# Loconet_in-out_v3.net
KiCad netlist of a schematic drawn in EAGLE
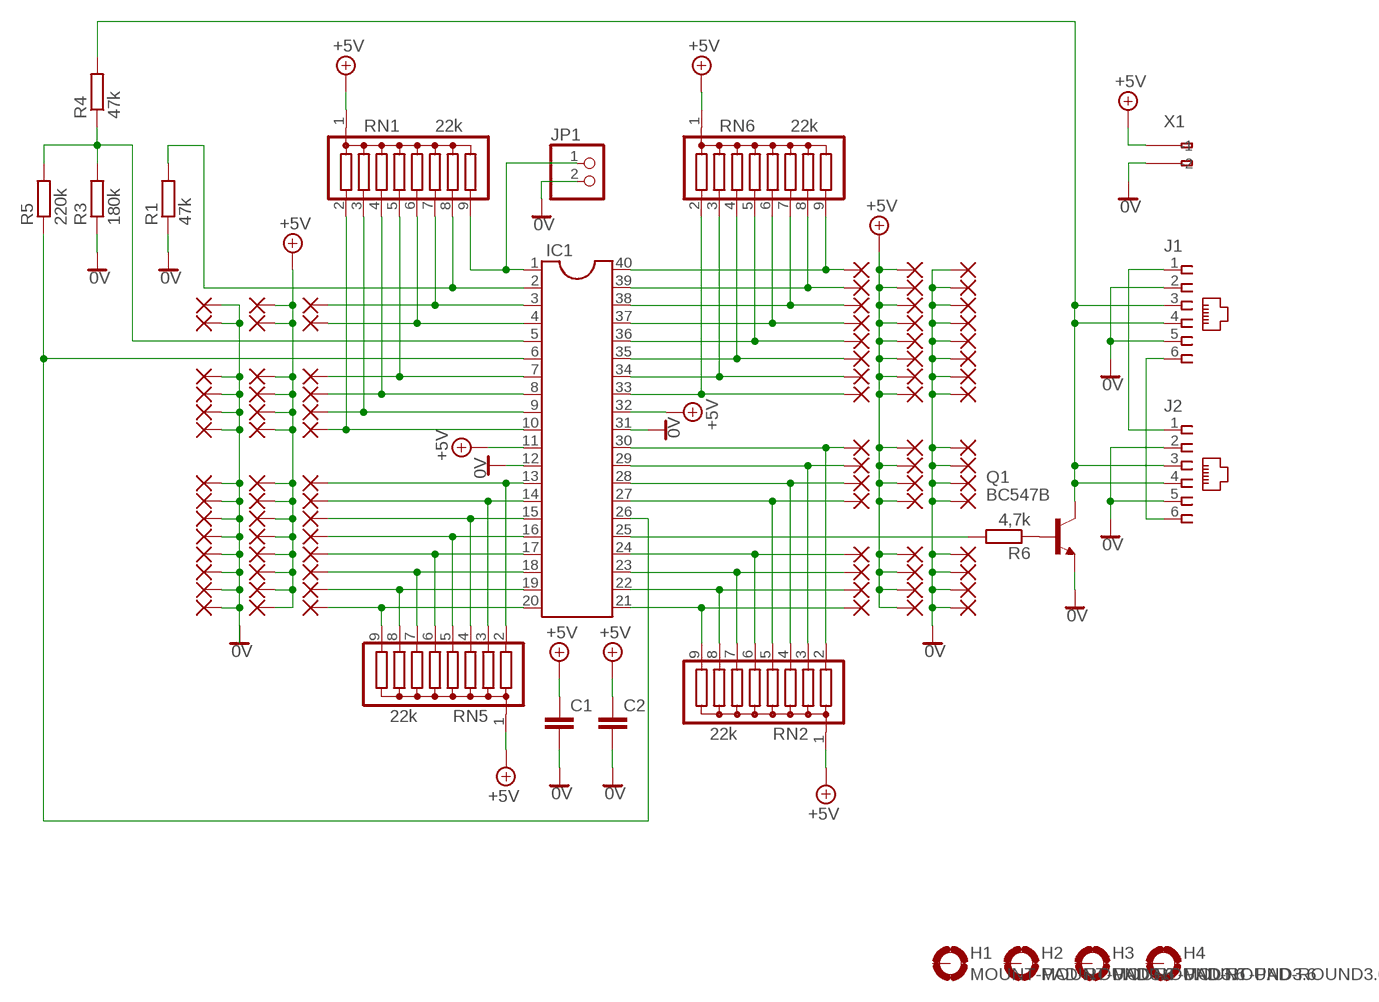
[diagram p0: schematic, sheet 1]

(export (version "E")
  (design (tool "Eeschema 10.0.6"))
  (components
    (comp (ref "0")
      (value "2,15/1,0")
      (footprint "eagle-import:2,15_1,0")
      (libsource (lib "eagle-import") (part "2,15/1,0"))
    )
    (comp (ref "1")
      (value "1")
      (footprint "eagle-import:2,15_1,0")
      (libsource (lib "eagle-import") (part "2,15/1,0"))
    )
    (comp (ref "2")
      (value "2,15/1,0")
      (footprint "eagle-import:2,15_1,0")
      (libsource (lib "eagle-import") (part "2,15/1,0"))
    )
    (comp (ref "3")
      (value "2,15/1,0")
      (footprint "eagle-import:2,15_1,0")
      (libsource (lib "eagle-import") (part "2,15/1,0"))
    )
    (comp (ref "4")
      (value "2,15/1,0")
      (footprint "eagle-import:2,15_1,0")
      (libsource (lib "eagle-import") (part "2,15/1,0"))
    )
    (comp (ref "5")
      (value "2,15/1,0")
      (footprint "eagle-import:2,15_1,0")
      (libsource (lib "eagle-import") (part "2,15/1,0"))
    )
    (comp (ref "6")
      (value "2,15/1,0")
      (footprint "eagle-import:2,15_1,0")
      (libsource (lib "eagle-import") (part "2,15/1,0"))
    )
    (comp (ref "7")
      (value "2,15/1,0")
      (footprint "eagle-import:2,15_1,0")
      (libsource (lib "eagle-import") (part "2,15/1,0"))
    )
    (comp (ref "8")
      (value "2,15/1,0")
      (footprint "eagle-import:2,15_1,0")
      (libsource (lib "eagle-import") (part "2,15/1,0"))
    )
    (comp (ref "9")
      (value "2,15/1,0")
      (footprint "eagle-import:2,15_1,0")
      (libsource (lib "eagle-import") (part "2,15/1,0"))
    )
    (comp (ref "10")
      (value "2,15/1,0")
      (footprint "eagle-import:2,15_1,0")
      (libsource (lib "eagle-import") (part "2,15/1,0"))
    )
    (comp (ref "11")
      (value "2,15/1,0")
      (footprint "eagle-import:2,15_1,0")
      (libsource (lib "eagle-import") (part "2,15/1,0"))
    )
    (comp (ref "12")
      (value "2,15/1,0")
      (footprint "eagle-import:2,15_1,0")
      (libsource (lib "eagle-import") (part "2,15/1,0"))
    )
    (comp (ref "13")
      (value "2,15/1,0")
      (footprint "eagle-import:2,15_1,0")
      (libsource (lib "eagle-import") (part "2,15/1,0"))
    )
    (comp (ref "14")
      (value "2,15/1,0")
      (footprint "eagle-import:2,15_1,0")
      (libsource (lib "eagle-import") (part "2,15/1,0"))
    )
    (comp (ref "15")
      (value "2,15/1,0")
      (footprint "eagle-import:2,15_1,0")
      (libsource (lib "eagle-import") (part "2,15/1,0"))
    )
    (comp (ref "16")
      (value "2,15/1,0")
      (footprint "eagle-import:2,15_1,0")
      (libsource (lib "eagle-import") (part "2,15/1,0"))
    )
    (comp (ref "17")
      (value "2,15/1,0")
      (footprint "eagle-import:2,15_1,0")
      (libsource (lib "eagle-import") (part "2,15/1,0"))
    )
    (comp (ref "18")
      (value "2,15/1,0")
      (footprint "eagle-import:2,15_1,0")
      (libsource (lib "eagle-import") (part "2,15/1,0"))
    )
    (comp (ref "19")
      (value "2,15/1,0")
      (footprint "eagle-import:2,15_1,0")
      (libsource (lib "eagle-import") (part "2,15/1,0"))
    )
    (comp (ref "20")
      (value "2,15/1,0")
      (footprint "eagle-import:2,15_1,0")
      (libsource (lib "eagle-import") (part "2,15/1,0"))
    )
    (comp (ref "21")
      (value "2,15/1,0")
      (footprint "eagle-import:2,15_1,0")
      (libsource (lib "eagle-import") (part "2,15/1,0"))
    )
    (comp (ref "22")
      (value "2,15/1,0")
      (footprint "eagle-import:2,15_1,0")
      (libsource (lib "eagle-import") (part "2,15/1,0"))
    )
    (comp (ref "23")
      (value "2,15/1,0")
      (footprint "eagle-import:2,15_1,0")
      (libsource (lib "eagle-import") (part "2,15/1,0"))
    )
    (comp (ref "24")
      (value "2,15/1,0")
      (footprint "eagle-import:2,15_1,0")
      (libsource (lib "eagle-import") (part "2,15/1,0"))
    )
    (comp (ref "25")
      (value "2,15/1,0")
      (footprint "eagle-import:2,15_1,0")
      (libsource (lib "eagle-import") (part "2,15/1,0"))
    )
    (comp (ref "26")
      (value "2,15/1,0")
      (footprint "eagle-import:2,15_1,0")
      (libsource (lib "eagle-import") (part "2,15/1,0"))
    )
    (comp (ref "27")
      (value "2,15/1,0")
      (footprint "eagle-import:2,15_1,0")
      (libsource (lib "eagle-import") (part "2,15/1,0"))
    )
    (comp (ref "28")
      (value "2,15/1,0")
      (footprint "eagle-import:2,15_1,0")
      (libsource (lib "eagle-import") (part "2,15/1,0"))
    )
    (comp (ref "29")
      (value "2,15/1,0")
      (footprint "eagle-import:2,15_1,0")
      (libsource (lib "eagle-import") (part "2,15/1,0"))
    )
    (comp (ref "30")
      (value "2,15/1,0")
      (footprint "eagle-import:2,15_1,0")
      (libsource (lib "eagle-import") (part "2,15/1,0"))
    )
    (comp (ref "C1")
      (value "C-EU025-024X044")
      (footprint "eagle-import:C025-024X044")
      (libsource (lib "eagle-import") (part "C-EU025-024X044"))
    )
    (comp (ref "C2")
      (value "C-EU025-024X044")
      (footprint "eagle-import:C025-024X044")
      (libsource (lib "eagle-import") (part "C-EU025-024X044"))
    )
    (comp (ref "H1")
      (value "MOUNT-PAD-ROUND3.6")
      (footprint "eagle-import:3,6-PAD")
      (libsource (lib "eagle-import") (part "MOUNT-PAD-ROUND3.6"))
    )
    (comp (ref "H2")
      (value "MOUNT-PAD-ROUND3.6")
      (footprint "eagle-import:3,6-PAD")
      (libsource (lib "eagle-import") (part "MOUNT-PAD-ROUND3.6"))
    )
    (comp (ref "H3")
      (value "MOUNT-PAD-ROUND3.6")
      (footprint "eagle-import:3,6-PAD")
      (libsource (lib "eagle-import") (part "MOUNT-PAD-ROUND3.6"))
    )
    (comp (ref "H4")
      (value "MOUNT-PAD-ROUND3.6")
      (footprint "eagle-import:3,6-PAD")
      (libsource (lib "eagle-import") (part "MOUNT-PAD-ROUND3.6"))
    )
    (comp (ref "IC1")
      (value "DIL40")
      (footprint "eagle-import:DIL40")
      (libsource (lib "eagle-import") (part "DIL40"))
    )
    (comp (ref "J1")
      (value "520250-3")
      (footprint "eagle-import:520250-3")
      (libsource (lib "eagle-import") (part "520250-3"))
    )
    (comp (ref "J2")
      (value "520250-3")
      (footprint "eagle-import:520250-3")
      (libsource (lib "eagle-import") (part "520250-3"))
    )
    (comp (ref "JP1")
      (value "PINHD-1X2")
      (footprint "eagle-import:1X02")
      (libsource (lib "eagle-import") (part "PINHD-1X2"))
    )
    (comp (ref "PAD1")
      (value "2,15/1,0")
      (footprint "eagle-import:2,15_1,0")
      (libsource (lib "eagle-import") (part "2,15/1,0"))
    )
    (comp (ref "PAD2")
      (value "2,15/1,0")
      (footprint "eagle-import:2,15_1,0")
      (libsource (lib "eagle-import") (part "2,15/1,0"))
    )
    (comp (ref "PAD3")
      (value "2,15/1,0")
      (footprint "eagle-import:2,15_1,0")
      (libsource (lib "eagle-import") (part "2,15/1,0"))
    )
    (comp (ref "PAD4")
      (value "2,15/1,0")
      (footprint "eagle-import:2,15_1,0")
      (libsource (lib "eagle-import") (part "2,15/1,0"))
    )
    (comp (ref "PAD5")
      (value "2,15/1,0")
      (footprint "eagle-import:2,15_1,0")
      (libsource (lib "eagle-import") (part "2,15/1,0"))
    )
    (comp (ref "PAD6")
      (value "2,15/1,0")
      (footprint "eagle-import:2,15_1,0")
      (libsource (lib "eagle-import") (part "2,15/1,0"))
    )
    (comp (ref "PAD7")
      (value "2,15/1,0")
      (footprint "eagle-import:2,15_1,0")
      (libsource (lib "eagle-import") (part "2,15/1,0"))
    )
    (comp (ref "PAD8")
      (value "2,15/1,0")
      (footprint "eagle-import:2,15_1,0")
      (libsource (lib "eagle-import") (part "2,15/1,0"))
    )
    (comp (ref "PAD9")
      (value "2,15/1,0")
      (footprint "eagle-import:2,15_1,0")
      (libsource (lib "eagle-import") (part "2,15/1,0"))
    )
    (comp (ref "PAD10")
      (value "2,15/1,0")
      (footprint "eagle-import:2,15_1,0")
      (libsource (lib "eagle-import") (part "2,15/1,0"))
    )
    (comp (ref "PAD11")
      (value "2,15/1,0")
      (footprint "eagle-import:2,15_1,0")
      (libsource (lib "eagle-import") (part "2,15/1,0"))
    )
    (comp (ref "PAD12")
      (value "2,15/1,0")
      (footprint "eagle-import:2,15_1,0")
      (libsource (lib "eagle-import") (part "2,15/1,0"))
    )
    (comp (ref "PAD13")
      (value "2,15/1,0")
      (footprint "eagle-import:2,15_1,0")
      (libsource (lib "eagle-import") (part "2,15/1,0"))
    )
    (comp (ref "PAD14")
      (value "2,15/1,0")
      (footprint "eagle-import:2,15_1,0")
      (libsource (lib "eagle-import") (part "2,15/1,0"))
    )
    (comp (ref "PAD15")
      (value "2,15/1,0")
      (footprint "eagle-import:2,15_1,0")
      (libsource (lib "eagle-import") (part "2,15/1,0"))
    )
    (comp (ref "PAD16")
      (value "2,15/1,0")
      (footprint "eagle-import:2,15_1,0")
      (libsource (lib "eagle-import") (part "2,15/1,0"))
    )
    (comp (ref "PAD17")
      (value "2,15/1,0")
      (footprint "eagle-import:2,15_1,0")
      (libsource (lib "eagle-import") (part "2,15/1,0"))
    )
    (comp (ref "PAD18")
      (value "2,15/1,0")
      (footprint "eagle-import:2,15_1,0")
      (libsource (lib "eagle-import") (part "2,15/1,0"))
    )
    (comp (ref "PAD19")
      (value "2,15/1,0")
      (footprint "eagle-import:2,15_1,0")
      (libsource (lib "eagle-import") (part "2,15/1,0"))
    )
    (comp (ref "PAD20")
      (value "2,15/1,0")
      (footprint "eagle-import:2,15_1,0")
      (libsource (lib "eagle-import") (part "2,15/1,0"))
    )
    (comp (ref "PAD21")
      (value "2,15/1,0")
      (footprint "eagle-import:2,15_1,0")
      (libsource (lib "eagle-import") (part "2,15/1,0"))
    )
    (comp (ref "PAD22")
      (value "2,15/1,0")
      (footprint "eagle-import:2,15_1,0")
      (libsource (lib "eagle-import") (part "2,15/1,0"))
    )
    (comp (ref "PAD23")
      (value "2,15/1,0")
      (footprint "eagle-import:2,15_1,0")
      (libsource (lib "eagle-import") (part "2,15/1,0"))
    )
    (comp (ref "PAD24")
      (value "2,15/1,0")
      (footprint "eagle-import:2,15_1,0")
      (libsource (lib "eagle-import") (part "2,15/1,0"))
    )
    (comp (ref "PAD25")
      (value "2,15/1,0")
      (footprint "eagle-import:2,15_1,0")
      (libsource (lib "eagle-import") (part "2,15/1,0"))
    )
    (comp (ref "PAD26")
      (value "2,15/1,0")
      (footprint "eagle-import:2,15_1,0")
      (libsource (lib "eagle-import") (part "2,15/1,0"))
    )
    (comp (ref "PAD27")
      (value "2,15/1,0")
      (footprint "eagle-import:2,15_1,0")
      (libsource (lib "eagle-import") (part "2,15/1,0"))
    )
    (comp (ref "PAD28")
      (value "2,15/1,0")
      (footprint "eagle-import:2,15_1,0")
      (libsource (lib "eagle-import") (part "2,15/1,0"))
    )
    (comp (ref "PAD29")
      (value "2,15/1,0")
      (footprint "eagle-import:2,15_1,0")
      (libsource (lib "eagle-import") (part "2,15/1,0"))
    )
    (comp (ref "PAD30")
      (value "2,15/1,0")
      (footprint "eagle-import:2,15_1,0")
      (libsource (lib "eagle-import") (part "2,15/1,0"))
    )
    (comp (ref "PAD33")
      (value "2,15/1,0")
      (footprint "eagle-import:2,15_1,0")
      (libsource (lib "eagle-import") (part "2,15/1,0"))
    )
    (comp (ref "PAD35")
      (value "2,15/1,0")
      (footprint "eagle-import:2,15_1,0")
      (libsource (lib "eagle-import") (part "2,15/1,0"))
    )
    (comp (ref "PAD37")
      (value "2,15/1,0")
      (footprint "eagle-import:2,15_1,0")
      (libsource (lib "eagle-import") (part "2,15/1,0"))
    )
    (comp (ref "PAD39")
      (value "2,15/1,0")
      (footprint "eagle-import:2,15_1,0")
      (libsource (lib "eagle-import") (part "2,15/1,0"))
    )
    (comp (ref "PAD41")
      (value "2,15/1,0")
      (footprint "eagle-import:2,15_1,0")
      (libsource (lib "eagle-import") (part "2,15/1,0"))
    )
    (comp (ref "PAD43")
      (value "2,15/1,0")
      (footprint "eagle-import:2,15_1,0")
      (libsource (lib "eagle-import") (part "2,15/1,0"))
    )
    (comp (ref "PAD52")
      (value "2,15/1,0")
      (footprint "eagle-import:2,15_1,0")
      (libsource (lib "eagle-import") (part "2,15/1,0"))
    )
    (comp (ref "PAD53")
      (value "2,15/1,0")
      (footprint "eagle-import:2,15_1,0")
      (libsource (lib "eagle-import") (part "2,15/1,0"))
    )
    (comp (ref "PAD54")
      (value "2,15/1,0")
      (footprint "eagle-import:2,15_1,0")
      (libsource (lib "eagle-import") (part "2,15/1,0"))
    )
    (comp (ref "PAD55")
      (value "2,15/1,0")
      (footprint "eagle-import:2,15_1,0")
      (libsource (lib "eagle-import") (part "2,15/1,0"))
    )
    (comp (ref "PAD56")
      (value "2,15/1,0")
      (footprint "eagle-import:2,15_1,0")
      (libsource (lib "eagle-import") (part "2,15/1,0"))
    )
    (comp (ref "PAD57")
      (value "2,15/1,0")
      (footprint "eagle-import:2,15_1,0")
      (libsource (lib "eagle-import") (part "2,15/1,0"))
    )
    (comp (ref "PAD58")
      (value "2,15/1,0")
      (footprint "eagle-import:2,15_1,0")
      (libsource (lib "eagle-import") (part "2,15/1,0"))
    )
    (comp (ref "PAD59")
      (value "2,15/1,0")
      (footprint "eagle-import:2,15_1,0")
      (libsource (lib "eagle-import") (part "2,15/1,0"))
    )
    (comp (ref "PAD60")
      (value "2,15/1,0")
      (footprint "eagle-import:2,15_1,0")
      (libsource (lib "eagle-import") (part "2,15/1,0"))
    )
    (comp (ref "PAD61")
      (value "2,15/1,0")
      (footprint "eagle-import:2,15_1,0")
      (libsource (lib "eagle-import") (part "2,15/1,0"))
    )
    (comp (ref "PAD62")
      (value "2,15/1,0")
      (footprint "eagle-import:2,15_1,0")
      (libsource (lib "eagle-import") (part "2,15/1,0"))
    )
    (comp (ref "PAD63")
      (value "2,15/1,0")
      (footprint "eagle-import:2,15_1,0")
      (libsource (lib "eagle-import") (part "2,15/1,0"))
    )
    (comp (ref "PAD64")
      (value "2,15/1,0")
      (footprint "eagle-import:2,15_1,0")
      (libsource (lib "eagle-import") (part "2,15/1,0"))
    )
    (comp (ref "PAD65")
      (value "2,15/1,0")
      (footprint "eagle-import:2,15_1,0")
      (libsource (lib "eagle-import") (part "2,15/1,0"))
    )
    (comp (ref "PAD66")
      (value "2,15/1,0")
      (footprint "eagle-import:2,15_1,0")
      (libsource (lib "eagle-import") (part "2,15/1,0"))
    )
    (comp (ref "PAD67")
      (value "2,15/1,0")
      (footprint "eagle-import:2,15_1,0")
      (libsource (lib "eagle-import") (part "2,15/1,0"))
    )
    (comp (ref "PAD68")
      (value "2,15/1,0")
      (footprint "eagle-import:2,15_1,0")
      (libsource (lib "eagle-import") (part "2,15/1,0"))
    )
    (comp (ref "PAD69")
      (value "2,15/1,0")
      (footprint "eagle-import:2,15_1,0")
      (libsource (lib "eagle-import") (part "2,15/1,0"))
    )
    (comp (ref "PAD70")
      (value "2,15/1,0")
      (footprint "eagle-import:2,15_1,0")
      (libsource (lib "eagle-import") (part "2,15/1,0"))
    )
    (comp (ref "PAD71")
      (value "2,15/1,0")
      (footprint "eagle-import:2,15_1,0")
      (libsource (lib "eagle-import") (part "2,15/1,0"))
    )
    (comp (ref "PAD72")
      (value "2,15/1,0")
      (footprint "eagle-import:2,15_1,0")
      (libsource (lib "eagle-import") (part "2,15/1,0"))
    )
    (comp (ref "PAD73")
      (value "2,15/1,0")
      (footprint "eagle-import:2,15_1,0")
      (libsource (lib "eagle-import") (part "2,15/1,0"))
    )
    (comp (ref "PAD74")
      (value "2,15/1,0")
      (footprint "eagle-import:2,15_1,0")
      (libsource (lib "eagle-import") (part "2,15/1,0"))
    )
    (comp (ref "Q1")
      (value "BC547B")
      (footprint "eagle-import:TO92")
      (libsource (lib "eagle-import") (part "BC547B"))
    )
    (comp (ref "R1")
      (value "47k")
      (footprint "eagle-import:0204_7")
      (libsource (lib "eagle-import") (part "R-EU_0204/7"))
    )
    (comp (ref "R3")
      (value "180k")
      (footprint "eagle-import:0204_7")
      (libsource (lib "eagle-import") (part "R-EU_0204/7"))
    )
    (comp (ref "R4")
      (value "47k")
      (footprint "eagle-import:0204_7")
      (libsource (lib "eagle-import") (part "R-EU_0204/7"))
    )
    (comp (ref "R5")
      (value "220k")
      (footprint "eagle-import:0204_7")
      (libsource (lib "eagle-import") (part "R-EU_0204/7"))
    )
    (comp (ref "R6")
      (value "4,7k")
      (footprint "eagle-import:0204_7")
      (libsource (lib "eagle-import") (part "R-EU_0204/7"))
    )
    (comp (ref "RN1")
      (value "22k")
      (footprint "eagle-import:SIL9")
      (libsource (lib "eagle-import") (part "G08R"))
    )
    (comp (ref "RN2")
      (value "22k")
      (footprint "eagle-import:SIL9")
      (libsource (lib "eagle-import") (part "G08R"))
    )
    (comp (ref "RN5")
      (value "22k")
      (footprint "eagle-import:SIL9")
      (libsource (lib "eagle-import") (part "G08R"))
    )
    (comp (ref "RN6")
      (value "22k")
      (footprint "eagle-import:SIL9")
      (libsource (lib "eagle-import") (part "G08R"))
    )
    (comp (ref "X1")
      (value "233-102")
      (footprint "eagle-import:233-102")
      (libsource (lib "eagle-import") (part "233-102"))
    )
  )
  (nets
    (net (code "1") (name "+5V") (class "Default")
      (node (ref "0") (pin "1") (pinfunction "P_1") (pintype "passive"))
      (node (ref "C1") (pin "1") (pinfunction "1_1") (pintype "passive"))
      (node (ref "C2") (pin "1") (pinfunction "1_1") (pintype "passive"))
      (node (ref "IC1") (pin "11") (pinfunction "11_11") (pintype "passive"))
      (node (ref "IC1") (pin "32") (pinfunction "32_32") (pintype "passive"))
      (node (ref "PAD33") (pin "1") (pinfunction "P_1") (pintype "passive"))
      (node (ref "PAD35") (pin "1") (pinfunction "P_1") (pintype "passive"))
      (node (ref "PAD37") (pin "1") (pinfunction "P_1") (pintype "passive"))
      (node (ref "PAD39") (pin "1") (pinfunction "P_1") (pintype "passive"))
      (node (ref "PAD41") (pin "1") (pinfunction "P_1") (pintype "passive"))
      (node (ref "PAD43") (pin "1") (pinfunction "P_1") (pintype "passive"))
      (node (ref "PAD52") (pin "1") (pinfunction "P_1") (pintype "passive"))
      (node (ref "PAD53") (pin "1") (pinfunction "P_1") (pintype "passive"))
      (node (ref "PAD54") (pin "1") (pinfunction "P_1") (pintype "passive"))
      (node (ref "PAD55") (pin "1") (pinfunction "P_1") (pintype "passive"))
      (node (ref "PAD56") (pin "1") (pinfunction "P_1") (pintype "passive"))
      (node (ref "PAD57") (pin "1") (pinfunction "P_1") (pintype "passive"))
      (node (ref "PAD58") (pin "1") (pinfunction "P_1") (pintype "passive"))
      (node (ref "PAD59") (pin "1") (pinfunction "P_1") (pintype "passive"))
      (node (ref "PAD60") (pin "1") (pinfunction "P_1") (pintype "passive"))
      (node (ref "PAD61") (pin "1") (pinfunction "P_1") (pintype "passive"))
      (node (ref "PAD62") (pin "1") (pinfunction "P_1") (pintype "passive"))
      (node (ref "PAD63") (pin "1") (pinfunction "P_1") (pintype "passive"))
      (node (ref "PAD64") (pin "1") (pinfunction "P_1") (pintype "passive"))
      (node (ref "PAD65") (pin "1") (pinfunction "P_1") (pintype "passive"))
      (node (ref "PAD66") (pin "1") (pinfunction "P_1") (pintype "passive"))
      (node (ref "PAD67") (pin "1") (pinfunction "P_1") (pintype "passive"))
      (node (ref "PAD68") (pin "1") (pinfunction "P_1") (pintype "passive"))
      (node (ref "PAD69") (pin "1") (pinfunction "P_1") (pintype "passive"))
      (node (ref "PAD70") (pin "1") (pinfunction "P_1") (pintype "passive"))
      (node (ref "PAD71") (pin "1") (pinfunction "P_1") (pintype "passive"))
      (node (ref "PAD72") (pin "1") (pinfunction "P_1") (pintype "passive"))
      (node (ref "PAD73") (pin "1") (pinfunction "P_1") (pintype "passive"))
      (node (ref "PAD74") (pin "1") (pinfunction "P_1") (pintype "passive"))
      (node (ref "RN1") (pin "1") (pinfunction "1_1") (pintype "passive"))
      (node (ref "RN2") (pin "1") (pinfunction "1_1") (pintype "passive"))
      (node (ref "RN5") (pin "1") (pinfunction "1_1") (pintype "passive"))
      (node (ref "RN6") (pin "1") (pinfunction "1_1") (pintype "passive"))
      (node (ref "X1") (pin "A1") (pinfunction "-1_A1") (pintype "passive"))
    )
    (net (code "2") (name "0V") (class "Default")
      (node (ref "1") (pin "1") (pinfunction "P_1") (pintype "passive"))
      (node (ref "10") (pin "1") (pinfunction "P_1") (pintype "passive"))
      (node (ref "11") (pin "1") (pinfunction "P_1") (pintype "passive"))
      (node (ref "12") (pin "1") (pinfunction "P_1") (pintype "passive"))
      (node (ref "13") (pin "1") (pinfunction "P_1") (pintype "passive"))
      (node (ref "14") (pin "1") (pinfunction "P_1") (pintype "passive"))
      (node (ref "15") (pin "1") (pinfunction "P_1") (pintype "passive"))
      (node (ref "16") (pin "1") (pinfunction "P_1") (pintype "passive"))
      (node (ref "17") (pin "1") (pinfunction "P_1") (pintype "passive"))
      (node (ref "18") (pin "1") (pinfunction "P_1") (pintype "passive"))
      (node (ref "19") (pin "1") (pinfunction "P_1") (pintype "passive"))
      (node (ref "2") (pin "1") (pinfunction "P_1") (pintype "passive"))
      (node (ref "20") (pin "1") (pinfunction "P_1") (pintype "passive"))
      (node (ref "21") (pin "1") (pinfunction "P_1") (pintype "passive"))
      (node (ref "22") (pin "1") (pinfunction "P_1") (pintype "passive"))
      (node (ref "23") (pin "1") (pinfunction "P_1") (pintype "passive"))
      (node (ref "24") (pin "1") (pinfunction "P_1") (pintype "passive"))
      (node (ref "25") (pin "1") (pinfunction "P_1") (pintype "passive"))
      (node (ref "26") (pin "1") (pinfunction "P_1") (pintype "passive"))
      (node (ref "27") (pin "1") (pinfunction "P_1") (pintype "passive"))
      (node (ref "28") (pin "1") (pinfunction "P_1") (pintype "passive"))
      (node (ref "29") (pin "1") (pinfunction "P_1") (pintype "passive"))
      (node (ref "3") (pin "1") (pinfunction "P_1") (pintype "passive"))
      (node (ref "30") (pin "1") (pinfunction "P_1") (pintype "passive"))
      (node (ref "4") (pin "1") (pinfunction "P_1") (pintype "passive"))
      (node (ref "5") (pin "1") (pinfunction "P_1") (pintype "passive"))
      (node (ref "6") (pin "1") (pinfunction "P_1") (pintype "passive"))
      (node (ref "7") (pin "1") (pinfunction "P_1") (pintype "passive"))
      (node (ref "8") (pin "1") (pinfunction "P_1") (pintype "passive"))
      (node (ref "9") (pin "1") (pinfunction "P_1") (pintype "passive"))
      (node (ref "C1") (pin "2") (pinfunction "2_2") (pintype "passive"))
      (node (ref "C2") (pin "2") (pinfunction "2_2") (pintype "passive"))
      (node (ref "IC1") (pin "12") (pinfunction "12_12") (pintype "passive"))
      (node (ref "IC1") (pin "31") (pinfunction "31_31") (pintype "passive"))
      (node (ref "J1") (pin "2") (pinfunction "2_2") (pintype "passive"))
      (node (ref "J1") (pin "5") (pinfunction "5_5") (pintype "passive"))
      (node (ref "J2") (pin "2") (pinfunction "2_2") (pintype "passive"))
      (node (ref "J2") (pin "5") (pinfunction "5_5") (pintype "passive"))
      (node (ref "JP1") (pin "2") (pinfunction "2_2") (pintype "passive"))
      (node (ref "Q1") (pin "1") (pinfunction "E_1") (pintype "passive"))
      (node (ref "R1") (pin "1") (pinfunction "1_1") (pintype "passive"))
      (node (ref "R3") (pin "1") (pinfunction "1_1") (pintype "passive"))
      (node (ref "X1") (pin "A2") (pinfunction "-2_A2") (pintype "passive"))
    )
    (net (code "3") (name "Net-(IC1-Pad1)") (class "Default")
      (node (ref "IC1") (pin "1") (pinfunction "1_1") (pintype "passive"))
      (node (ref "JP1") (pin "1") (pinfunction "1_1") (pintype "passive"))
      (node (ref "RN1") (pin "9") (pinfunction "9_9") (pintype "passive"))
    )
    (net (code "4") (name "Net-(IC1-Pad2)") (class "Default")
      (node (ref "IC1") (pin "2") (pinfunction "2_2") (pintype "passive"))
      (node (ref "R1") (pin "2") (pinfunction "2_2") (pintype "passive"))
      (node (ref "RN1") (pin "8") (pinfunction "8_8") (pintype "passive"))
    )
    (net (code "5") (name "Net-(IC1-Pad5)") (class "Default")
      (node (ref "IC1") (pin "5") (pinfunction "5_5") (pintype "passive"))
      (node (ref "R3") (pin "2") (pinfunction "2_2") (pintype "passive"))
      (node (ref "R4") (pin "1") (pinfunction "1_1") (pintype "passive"))
      (node (ref "R5") (pin "2") (pinfunction "2_2") (pintype "passive"))
    )
    (net (code "6") (name "Net-(IC1-Pad25)") (class "Default")
      (node (ref "IC1") (pin "25") (pinfunction "25_25") (pintype "passive"))
      (node (ref "R6") (pin "2") (pinfunction "2_2") (pintype "passive"))
    )
    (net (code "7") (name "Net-(IC1-Pad26)") (class "Default")
      (node (ref "IC1") (pin "26") (pinfunction "26_26") (pintype "passive"))
      (node (ref "IC1") (pin "6") (pinfunction "6_6") (pintype "passive"))
      (node (ref "R5") (pin "1") (pinfunction "1_1") (pintype "passive"))
    )
    (net (code "8") (name "Net-(J1-Pad1)") (class "Default")
      (node (ref "J1") (pin "1") (pinfunction "1_1") (pintype "passive"))
      (node (ref "J2") (pin "1") (pinfunction "1_1") (pintype "passive"))
    )
    (net (code "9") (name "Net-(J1-Pad6)") (class "Default")
      (node (ref "J1") (pin "6") (pinfunction "6_6") (pintype "passive"))
      (node (ref "J2") (pin "6") (pinfunction "6_6") (pintype "passive"))
    )
    (net (code "10") (name "Net-(PAD1-P)") (class "Default")
      (node (ref "IC1") (pin "3") (pinfunction "3_3") (pintype "passive"))
      (node (ref "PAD1") (pin "1") (pinfunction "P_1") (pintype "passive"))
      (node (ref "RN1") (pin "7") (pinfunction "7_7") (pintype "passive"))
    )
    (net (code "11") (name "Net-(PAD2-P)") (class "Default")
      (node (ref "IC1") (pin "4") (pinfunction "4_4") (pintype "passive"))
      (node (ref "PAD2") (pin "1") (pinfunction "P_1") (pintype "passive"))
      (node (ref "RN1") (pin "6") (pinfunction "6_6") (pintype "passive"))
    )
    (net (code "12") (name "Net-(PAD3-P)") (class "Default")
      (node (ref "IC1") (pin "7") (pinfunction "7_7") (pintype "passive"))
      (node (ref "PAD3") (pin "1") (pinfunction "P_1") (pintype "passive"))
      (node (ref "RN1") (pin "5") (pinfunction "5_5") (pintype "passive"))
    )
    (net (code "13") (name "Net-(PAD4-P)") (class "Default")
      (node (ref "IC1") (pin "8") (pinfunction "8_8") (pintype "passive"))
      (node (ref "PAD4") (pin "1") (pinfunction "P_1") (pintype "passive"))
      (node (ref "RN1") (pin "4") (pinfunction "4_4") (pintype "passive"))
    )
    (net (code "14") (name "Net-(PAD5-P)") (class "Default")
      (node (ref "IC1") (pin "9") (pinfunction "9_9") (pintype "passive"))
      (node (ref "PAD5") (pin "1") (pinfunction "P_1") (pintype "passive"))
      (node (ref "RN1") (pin "3") (pinfunction "3_3") (pintype "passive"))
    )
    (net (code "15") (name "Net-(PAD6-P)") (class "Default")
      (node (ref "IC1") (pin "10") (pinfunction "10_10") (pintype "passive"))
      (node (ref "PAD6") (pin "1") (pinfunction "P_1") (pintype "passive"))
      (node (ref "RN1") (pin "2") (pinfunction "2_2") (pintype "passive"))
    )
    (net (code "16") (name "Net-(PAD7-P)") (class "Default")
      (node (ref "IC1") (pin "40") (pinfunction "40_40") (pintype "passive"))
      (node (ref "PAD7") (pin "1") (pinfunction "P_1") (pintype "passive"))
      (node (ref "RN6") (pin "9") (pinfunction "9_9") (pintype "passive"))
    )
    (net (code "17") (name "Net-(PAD8-P)") (class "Default")
      (node (ref "IC1") (pin "39") (pinfunction "39_39") (pintype "passive"))
      (node (ref "PAD8") (pin "1") (pinfunction "P_1") (pintype "passive"))
      (node (ref "RN6") (pin "8") (pinfunction "8_8") (pintype "passive"))
    )
    (net (code "18") (name "Net-(PAD9-P)") (class "Default")
      (node (ref "IC1") (pin "38") (pinfunction "38_38") (pintype "passive"))
      (node (ref "PAD9") (pin "1") (pinfunction "P_1") (pintype "passive"))
      (node (ref "RN6") (pin "7") (pinfunction "7_7") (pintype "passive"))
    )
    (net (code "19") (name "Net-(PAD10-P)") (class "Default")
      (node (ref "IC1") (pin "37") (pinfunction "37_37") (pintype "passive"))
      (node (ref "PAD10") (pin "1") (pinfunction "P_1") (pintype "passive"))
      (node (ref "RN6") (pin "6") (pinfunction "6_6") (pintype "passive"))
    )
    (net (code "20") (name "Net-(PAD11-P)") (class "Default")
      (node (ref "IC1") (pin "36") (pinfunction "36_36") (pintype "passive"))
      (node (ref "PAD11") (pin "1") (pinfunction "P_1") (pintype "passive"))
      (node (ref "RN6") (pin "5") (pinfunction "5_5") (pintype "passive"))
    )
    (net (code "21") (name "Net-(PAD12-P)") (class "Default")
      (node (ref "IC1") (pin "35") (pinfunction "35_35") (pintype "passive"))
      (node (ref "PAD12") (pin "1") (pinfunction "P_1") (pintype "passive"))
      (node (ref "RN6") (pin "4") (pinfunction "4_4") (pintype "passive"))
    )
    (net (code "22") (name "Net-(PAD13-P)") (class "Default")
      (node (ref "IC1") (pin "34") (pinfunction "34_34") (pintype "passive"))
      (node (ref "PAD13") (pin "1") (pinfunction "P_1") (pintype "passive"))
      (node (ref "RN6") (pin "3") (pinfunction "3_3") (pintype "passive"))
    )
    (net (code "23") (name "Net-(PAD14-P)") (class "Default")
      (node (ref "IC1") (pin "33") (pinfunction "33_33") (pintype "passive"))
      (node (ref "PAD14") (pin "1") (pinfunction "P_1") (pintype "passive"))
      (node (ref "RN6") (pin "2") (pinfunction "2_2") (pintype "passive"))
    )
    (net (code "24") (name "Net-(PAD15-P)") (class "Default")
      (node (ref "IC1") (pin "30") (pinfunction "30_30") (pintype "passive"))
      (node (ref "PAD15") (pin "1") (pinfunction "P_1") (pintype "passive"))
      (node (ref "RN2") (pin "2") (pinfunction "2_2") (pintype "passive"))
    )
    (net (code "25") (name "Net-(PAD16-P)") (class "Default")
      (node (ref "IC1") (pin "29") (pinfunction "29_29") (pintype "passive"))
      (node (ref "PAD16") (pin "1") (pinfunction "P_1") (pintype "passive"))
      (node (ref "RN2") (pin "3") (pinfunction "3_3") (pintype "passive"))
    )
    (net (code "26") (name "Net-(PAD17-P)") (class "Default")
      (node (ref "IC1") (pin "28") (pinfunction "28_28") (pintype "passive"))
      (node (ref "PAD17") (pin "1") (pinfunction "P_1") (pintype "passive"))
      (node (ref "RN2") (pin "4") (pinfunction "4_4") (pintype "passive"))
    )
    (net (code "27") (name "Net-(PAD18-P)") (class "Default")
      (node (ref "IC1") (pin "27") (pinfunction "27_27") (pintype "passive"))
      (node (ref "PAD18") (pin "1") (pinfunction "P_1") (pintype "passive"))
      (node (ref "RN2") (pin "5") (pinfunction "5_5") (pintype "passive"))
    )
    (net (code "28") (name "Net-(PAD19-P)") (class "Default")
      (node (ref "IC1") (pin "24") (pinfunction "24_24") (pintype "passive"))
      (node (ref "PAD19") (pin "1") (pinfunction "P_1") (pintype "passive"))
      (node (ref "RN2") (pin "6") (pinfunction "6_6") (pintype "passive"))
    )
    (net (code "29") (name "Net-(PAD20-P)") (class "Default")
      (node (ref "IC1") (pin "23") (pinfunction "23_23") (pintype "passive"))
      (node (ref "PAD20") (pin "1") (pinfunction "P_1") (pintype "passive"))
      (node (ref "RN2") (pin "7") (pinfunction "7_7") (pintype "passive"))
    )
    (net (code "30") (name "Net-(PAD21-P)") (class "Default")
      (node (ref "IC1") (pin "22") (pinfunction "22_22") (pintype "passive"))
      (node (ref "PAD21") (pin "1") (pinfunction "P_1") (pintype "passive"))
      (node (ref "RN2") (pin "8") (pinfunction "8_8") (pintype "passive"))
    )
    (net (code "31") (name "Net-(PAD22-P)") (class "Default")
      (node (ref "IC1") (pin "21") (pinfunction "21_21") (pintype "passive"))
      (node (ref "PAD22") (pin "1") (pinfunction "P_1") (pintype "passive"))
      (node (ref "RN2") (pin "9") (pinfunction "9_9") (pintype "passive"))
    )
    (net (code "32") (name "Net-(PAD23-P)") (class "Default")
      (node (ref "IC1") (pin "20") (pinfunction "20_20") (pintype "passive"))
      (node (ref "PAD23") (pin "1") (pinfunction "P_1") (pintype "passive"))
      (node (ref "RN5") (pin "9") (pinfunction "9_9") (pintype "passive"))
    )
    (net (code "33") (name "Net-(PAD24-P)") (class "Default")
      (node (ref "IC1") (pin "19") (pinfunction "19_19") (pintype "passive"))
      (node (ref "PAD24") (pin "1") (pinfunction "P_1") (pintype "passive"))
      (node (ref "RN5") (pin "8") (pinfunction "8_8") (pintype "passive"))
    )
    (net (code "34") (name "Net-(PAD25-P)") (class "Default")
      (node (ref "IC1") (pin "18") (pinfunction "18_18") (pintype "passive"))
      (node (ref "PAD25") (pin "1") (pinfunction "P_1") (pintype "passive"))
      (node (ref "RN5") (pin "7") (pinfunction "7_7") (pintype "passive"))
    )
    (net (code "35") (name "Net-(PAD26-P)") (class "Default")
      (node (ref "IC1") (pin "17") (pinfunction "17_17") (pintype "passive"))
      (node (ref "PAD26") (pin "1") (pinfunction "P_1") (pintype "passive"))
      (node (ref "RN5") (pin "6") (pinfunction "6_6") (pintype "passive"))
    )
    (net (code "36") (name "Net-(PAD27-P)") (class "Default")
      (node (ref "IC1") (pin "16") (pinfunction "16_16") (pintype "passive"))
      (node (ref "PAD27") (pin "1") (pinfunction "P_1") (pintype "passive"))
      (node (ref "RN5") (pin "5") (pinfunction "5_5") (pintype "passive"))
    )
    (net (code "37") (name "Net-(PAD28-P)") (class "Default")
      (node (ref "IC1") (pin "15") (pinfunction "15_15") (pintype "passive"))
      (node (ref "PAD28") (pin "1") (pinfunction "P_1") (pintype "passive"))
      (node (ref "RN5") (pin "4") (pinfunction "4_4") (pintype "passive"))
    )
    (net (code "38") (name "Net-(PAD29-P)") (class "Default")
      (node (ref "IC1") (pin "14") (pinfunction "14_14") (pintype "passive"))
      (node (ref "PAD29") (pin "1") (pinfunction "P_1") (pintype "passive"))
      (node (ref "RN5") (pin "3") (pinfunction "3_3") (pintype "passive"))
    )
    (net (code "39") (name "Net-(PAD30-P)") (class "Default")
      (node (ref "IC1") (pin "13") (pinfunction "13_13") (pintype "passive"))
      (node (ref "PAD30") (pin "1") (pinfunction "P_1") (pintype "passive"))
      (node (ref "RN5") (pin "2") (pinfunction "2_2") (pintype "passive"))
    )
    (net (code "40") (name "Net-(Q1-B)") (class "Default")
      (node (ref "Q1") (pin "2") (pinfunction "B_2") (pintype "passive"))
      (node (ref "R6") (pin "1") (pinfunction "1_1") (pintype "passive"))
    )
    (net (code "41") (name "Net-(Q1-C)") (class "Default")
      (node (ref "J1") (pin "3") (pinfunction "3_3") (pintype "passive"))
      (node (ref "J1") (pin "4") (pinfunction "4_4") (pintype "passive"))
      (node (ref "J2") (pin "3") (pinfunction "3_3") (pintype "passive"))
      (node (ref "J2") (pin "4") (pinfunction "4_4") (pintype "passive"))
      (node (ref "Q1") (pin "3") (pinfunction "C_3") (pintype "passive"))
      (node (ref "R4") (pin "2") (pinfunction "2_2") (pintype "passive"))
    )
    (net (code "42") (name "unconnected-(H1-MOUNT-PadB3,6)") (class "Default")
      (node (ref "H1") (pin "B3,6") (pinfunction "MOUNT_B3,6") (pintype "passive"))
    )
    (net (code "43") (name "unconnected-(H2-MOUNT-PadB3,6)") (class "Default")
      (node (ref "H2") (pin "B3,6") (pinfunction "MOUNT_B3,6") (pintype "passive"))
    )
    (net (code "44") (name "unconnected-(H3-MOUNT-PadB3,6)") (class "Default")
      (node (ref "H3") (pin "B3,6") (pinfunction "MOUNT_B3,6") (pintype "passive"))
    )
    (net (code "45") (name "unconnected-(H4-MOUNT-PadB3,6)") (class "Default")
      (node (ref "H4") (pin "B3,6") (pinfunction "MOUNT_B3,6") (pintype "passive"))
    )
    (net (code "46") (name "unconnected-(X1-B-1-PadB1)") (class "Default")
      (node (ref "X1") (pin "B1") (pinfunction "B-1_B1") (pintype "passive"))
    )
    (net (code "47") (name "unconnected-(X1-B-2-PadB2)") (class "Default")
      (node (ref "X1") (pin "B2") (pinfunction "B-2_B2") (pintype "passive"))
    )
  )
)
